# PowerSwitch.net
KiCad netlist of a schematic drawn in Altium Designer
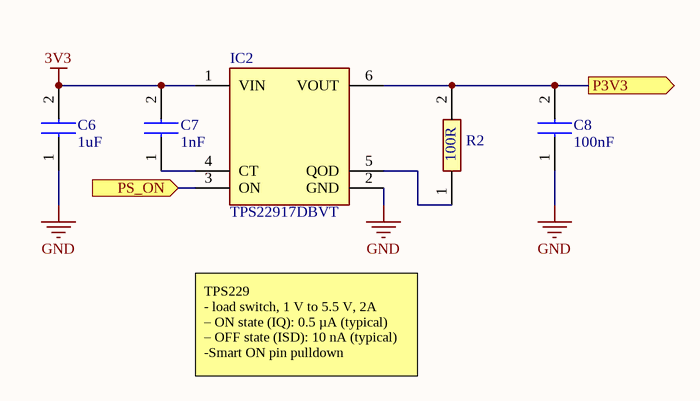
[diagram p0: PowerSwitch.SchDoc]

(export (version "E")
  (design (tool "Eeschema 10.0.6"))
  (components
    (comp (ref "C6")
      (value "1uF")
      (footprint "SamacSys:CAPC1608X90N")
      (description "Capacitor")
      (fields
        (field (name "MANUFACTURER_PART_NUMBER") "GRM188R61A105KA61D")
        (field (name "MOUSER PART NUMBER") "81-GRM39R105K10")
      )
      (libsource (lib "*") (part "GRM188R61A105KA61D"))
    )
    (comp (ref "C7")
      (value "1nF")
      (footprint "SamacSys:CAPC1005X70N")
      (description "Capacitor")
      (fields
        (field (name "MANUFACTURER_PART_NUMBER") "GRM155R61A102KA01D")
        (field (name "MOUSER PART NUMBER") "81-GRM155R61A102KA1D")
      )
      (libsource (lib "*") (part "GRM155R61A102KA01D"))
    )
    (comp (ref "C8")
      (value "100nF")
      (footprint "SamacSys:CAPC1005X70N")
      (description "Capacitor")
      (fields
        (field (name "MANUFACTURER_PART_NUMBER") "GRM155R61A104KA01D")
        (field (name "MOUSER PART NUMBER") "81-GRM155R61A104KA01")
      )
      (libsource (lib "*") (part "GRM155R61A104KA01D"))
    )
    (comp (ref "IC2")
      (value "TPS22917DBVT")
      (footprint "SamacSys:SOT95P280X145-6N")
      (description "Integrated Circuit")
      (fields (field (name "MOUSER PART NUMBER") "595-TPS22917DBVT"))
      (libsource (lib "SamacSys") (part "TPS22917DBVT"))
    )
    (comp (ref "R2")
      (value "100R")
      (footprint "SamacSys:RESC1608X55N")
      (description "Resistor")
      (fields
        (field (name "MANUFACTURER_PART_NUMBER") "ESR03EZPF1000")
        (field (name "MOUSER PART NUMBER") "755-ESR03EZPF1000")
      )
      (libsource (lib "*") (part "ESR03EZPF1000"))
    )
  )
  (nets
    (net (code "1") (name "/P3V3") (class "Default")
      (node (ref "C8") (pin "2") (pinfunction "2_2") (pintype "passive"))
      (node (ref "IC2") (pin "6") (pinfunction "VOUT_6") (pintype "passive"))
      (node (ref "R2") (pin "2") (pinfunction "2_2") (pintype "passive"))
    )
    (net (code "2") (name "/PS_ON") (class "Default")
      (node (ref "IC2") (pin "3") (pinfunction "ON_3") (pintype "passive"))
    )
    (net (code "3") (name "3V3") (class "Default")
      (node (ref "C6") (pin "2") (pinfunction "2_2") (pintype "passive"))
      (node (ref "C7") (pin "2") (pinfunction "2_2") (pintype "passive"))
      (node (ref "IC2") (pin "1") (pinfunction "VIN_1") (pintype "passive"))
    )
    (net (code "4") (name "GND") (class "Default")
      (node (ref "C6") (pin "1") (pinfunction "1_1") (pintype "passive"))
      (node (ref "C8") (pin "1") (pinfunction "1_1") (pintype "passive"))
      (node (ref "IC2") (pin "2") (pinfunction "GND_2") (pintype "passive"))
    )
    (net (code "5") (name "Net-(IC2-CT)") (class "Default")
      (node (ref "C7") (pin "1") (pinfunction "1_1") (pintype "passive"))
      (node (ref "IC2") (pin "4") (pinfunction "CT_4") (pintype "passive"))
    )
    (net (code "6") (name "Net-(IC2-QOD)") (class "Default")
      (node (ref "IC2") (pin "5") (pinfunction "QOD_5") (pintype "passive"))
      (node (ref "R2") (pin "1") (pinfunction "1_1") (pintype "passive"))
    )
  )
)
